# max78000_audio.net
KiCad netlist of a schematic drawn in EAGLE
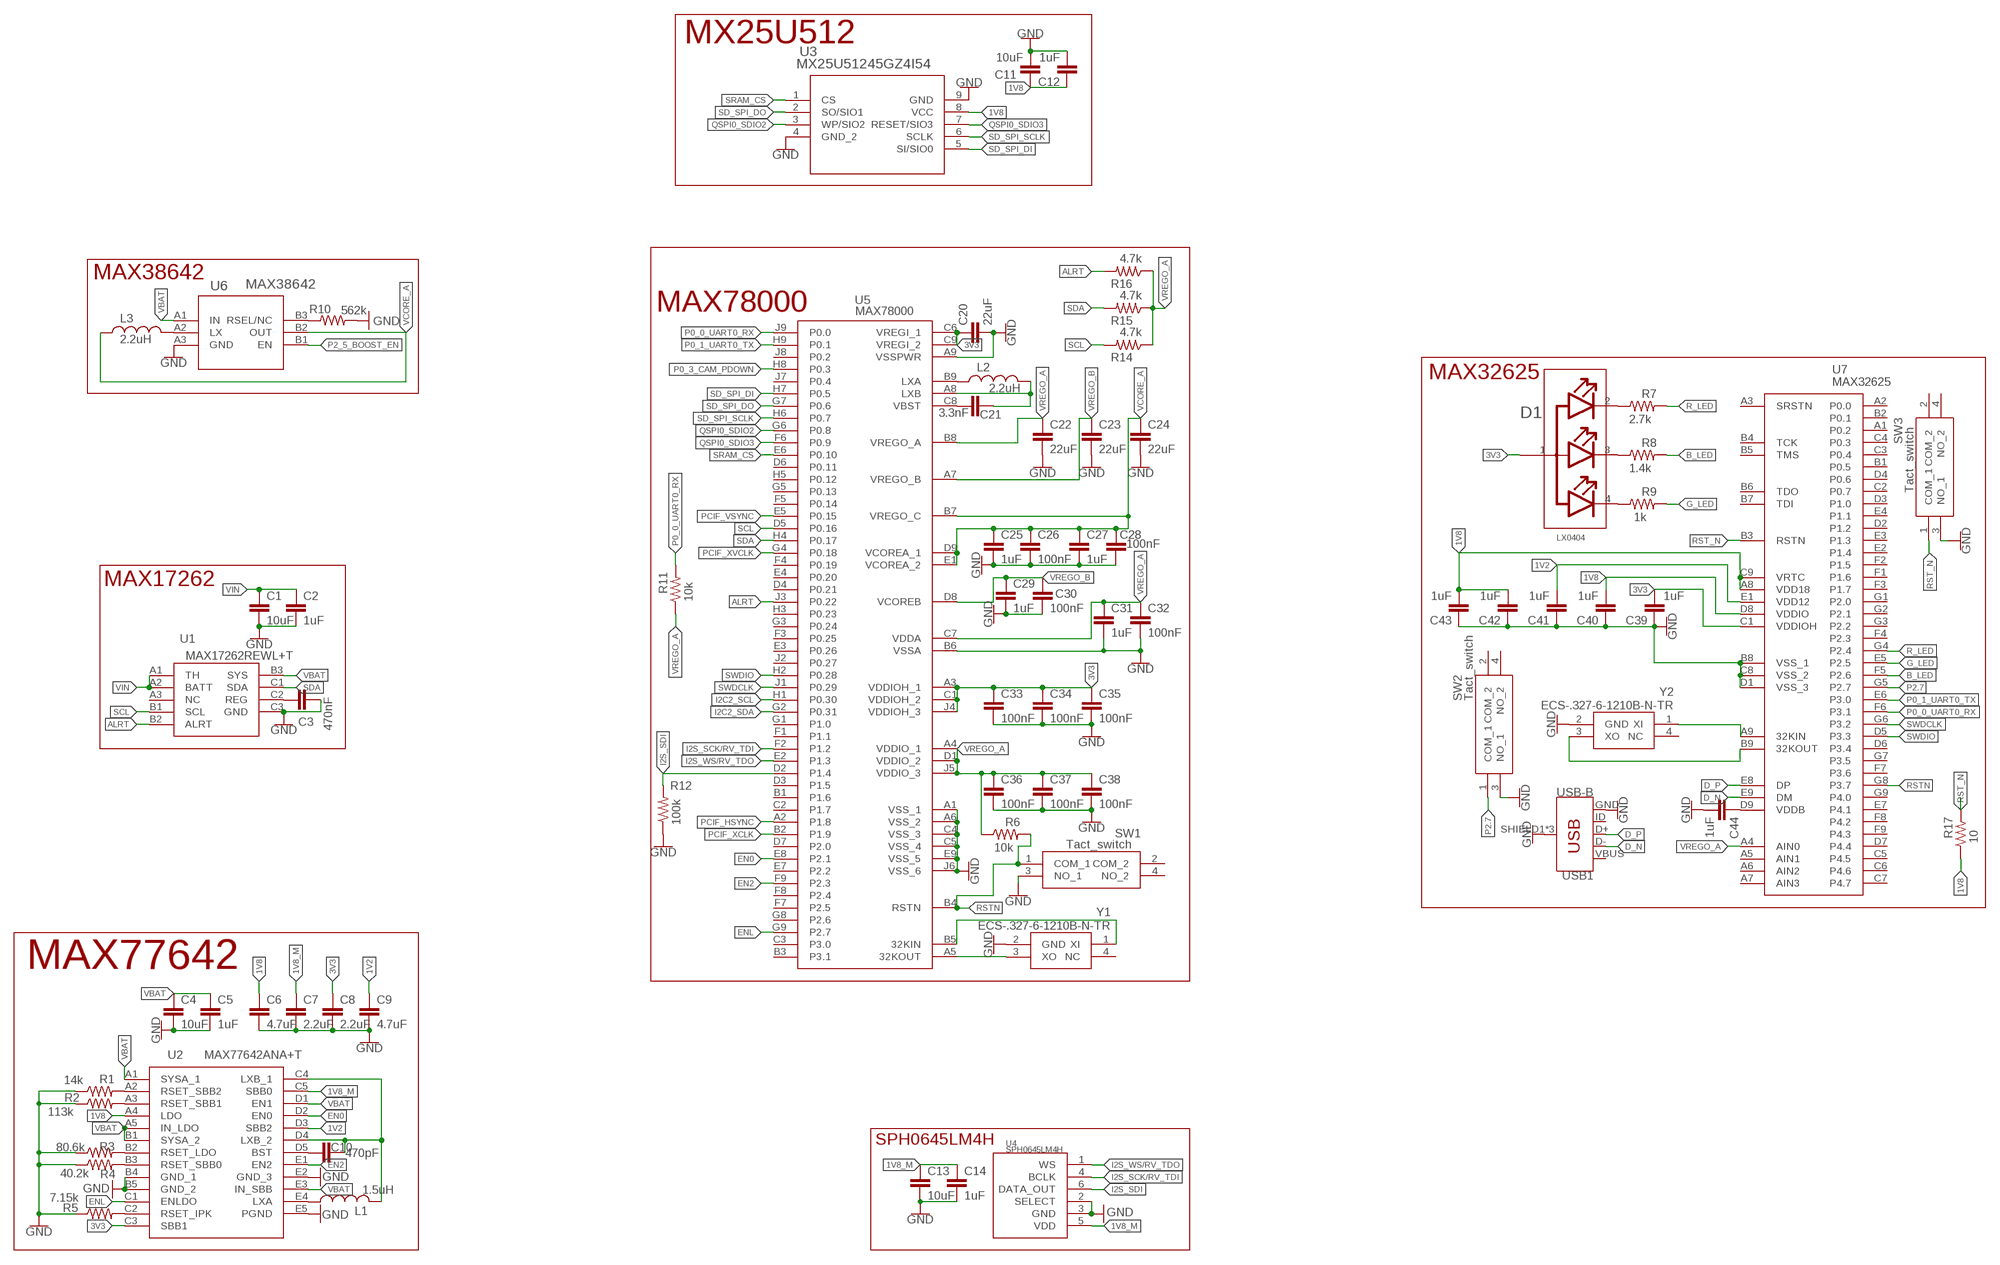
[diagram p0: schematic, sheet 1]

(export (version "E")
  (design (tool "Eeschema 10.0.6"))
  (components
    (comp (ref "C1")
      (value "10uF")
      (footprint "eagle-import:0402")
      (libsource (lib "eagle-import") (part "NPOL_SMD0402"))
    )
    (comp (ref "C2")
      (value "1uF")
      (footprint "eagle-import:0201")
      (libsource (lib "eagle-import") (part "NPOL_SMD0201"))
    )
    (comp (ref "C3")
      (value "470nF")
      (footprint "eagle-import:0201")
      (libsource (lib "eagle-import") (part "NPOL_SMD0201"))
    )
    (comp (ref "C4")
      (value "10uF")
      (footprint "eagle-import:0402")
      (libsource (lib "eagle-import") (part "NPOL_SMD0402"))
    )
    (comp (ref "C5")
      (value "1uF")
      (footprint "eagle-import:0201")
      (libsource (lib "eagle-import") (part "NPOL_SMD0201"))
    )
    (comp (ref "C6")
      (value "4.7uF")
      (footprint "eagle-import:0402")
      (libsource (lib "eagle-import") (part "NPOL_SMD0402"))
    )
    (comp (ref "C7")
      (value "2.2uF")
      (footprint "eagle-import:0402")
      (libsource (lib "eagle-import") (part "NPOL_SMD0402"))
    )
    (comp (ref "C8")
      (value "2.2uF")
      (footprint "eagle-import:0402")
      (libsource (lib "eagle-import") (part "NPOL_SMD0402"))
    )
    (comp (ref "C9")
      (value "4.7uF")
      (footprint "eagle-import:0402")
      (libsource (lib "eagle-import") (part "NPOL_SMD0402"))
    )
    (comp (ref "C10")
      (value "470pF")
      (footprint "eagle-import:0402")
      (libsource (lib "eagle-import") (part "NPOL_SMD0402"))
    )
    (comp (ref "C11")
      (value "10uF")
      (footprint "eagle-import:0201")
      (libsource (lib "eagle-import") (part "NPOL_SMD0201"))
    )
    (comp (ref "C12")
      (value "1uF")
      (footprint "eagle-import:0402")
      (libsource (lib "eagle-import") (part "NPOL_SMD0402"))
    )
    (comp (ref "C13")
      (value "10uF")
      (footprint "eagle-import:0402")
      (libsource (lib "eagle-import") (part "NPOL_SMD0402"))
    )
    (comp (ref "C14")
      (value "1uF")
      (footprint "eagle-import:0201")
      (libsource (lib "eagle-import") (part "NPOL_SMD0201"))
    )
    (comp (ref "C20")
      (value "22uF")
      (footprint "eagle-import:0603")
      (libsource (lib "eagle-import") (part "NPOL_SMD0603"))
    )
    (comp (ref "C21")
      (value "3.3nF")
      (footprint "eagle-import:0201")
      (libsource (lib "eagle-import") (part "NPOL_SMD0201"))
    )
    (comp (ref "C22")
      (value "22uF")
      (footprint "eagle-import:0603")
      (libsource (lib "eagle-import") (part "NPOL_SMD0603"))
    )
    (comp (ref "C23")
      (value "22uF")
      (footprint "eagle-import:0603")
      (libsource (lib "eagle-import") (part "NPOL_SMD0603"))
    )
    (comp (ref "C24")
      (value "22uF")
      (footprint "eagle-import:0603")
      (libsource (lib "eagle-import") (part "NPOL_SMD0603"))
    )
    (comp (ref "C25")
      (value "1uF")
      (footprint "eagle-import:0402")
      (libsource (lib "eagle-import") (part "NPOL_SMD0402"))
    )
    (comp (ref "C26")
      (value "100nF")
      (footprint "eagle-import:0201")
      (libsource (lib "eagle-import") (part "NPOL_SMD0201"))
    )
    (comp (ref "C27")
      (value "1uF")
      (footprint "eagle-import:0402")
      (libsource (lib "eagle-import") (part "NPOL_SMD0402"))
    )
    (comp (ref "C28")
      (value "100nF")
      (footprint "eagle-import:0201")
      (libsource (lib "eagle-import") (part "NPOL_SMD0201"))
    )
    (comp (ref "C29")
      (value "1uF")
      (footprint "eagle-import:0402")
      (libsource (lib "eagle-import") (part "NPOL_SMD0402"))
    )
    (comp (ref "C30")
      (value "100nF")
      (footprint "eagle-import:0201")
      (libsource (lib "eagle-import") (part "NPOL_SMD0201"))
    )
    (comp (ref "C31")
      (value "1uF")
      (footprint "eagle-import:0402")
      (libsource (lib "eagle-import") (part "NPOL_SMD0402"))
    )
    (comp (ref "C32")
      (value "100nF")
      (footprint "eagle-import:0201")
      (libsource (lib "eagle-import") (part "NPOL_SMD0201"))
    )
    (comp (ref "C33")
      (value "100nF")
      (footprint "eagle-import:0201")
      (libsource (lib "eagle-import") (part "NPOL_SMD0201"))
    )
    (comp (ref "C34")
      (value "100nF")
      (footprint "eagle-import:0201")
      (libsource (lib "eagle-import") (part "NPOL_SMD0201"))
    )
    (comp (ref "C35")
      (value "100nF")
      (footprint "eagle-import:0201")
      (libsource (lib "eagle-import") (part "NPOL_SMD0201"))
    )
    (comp (ref "C36")
      (value "100nF")
      (footprint "eagle-import:0201")
      (libsource (lib "eagle-import") (part "NPOL_SMD0201"))
    )
    (comp (ref "C37")
      (value "100nF")
      (footprint "eagle-import:0201")
      (libsource (lib "eagle-import") (part "NPOL_SMD0201"))
    )
    (comp (ref "C38")
      (value "100nF")
      (footprint "eagle-import:0201")
      (libsource (lib "eagle-import") (part "NPOL_SMD0201"))
    )
    (comp (ref "C39")
      (value "1uF")
      (footprint "eagle-import:0201")
      (libsource (lib "eagle-import") (part "NPOL_SMD0201"))
    )
    (comp (ref "C40")
      (value "1uF")
      (footprint "eagle-import:0201")
      (libsource (lib "eagle-import") (part "NPOL_SMD0201"))
    )
    (comp (ref "C41")
      (value "1uF")
      (footprint "eagle-import:0201")
      (libsource (lib "eagle-import") (part "NPOL_SMD0201"))
    )
    (comp (ref "C42")
      (value "1uF")
      (footprint "eagle-import:0201")
      (libsource (lib "eagle-import") (part "NPOL_SMD0201"))
    )
    (comp (ref "C43")
      (value "1uF")
      (footprint "eagle-import:0201")
      (libsource (lib "eagle-import") (part "NPOL_SMD0201"))
    )
    (comp (ref "C44")
      (value "1uF")
      (footprint "eagle-import:0201")
      (libsource (lib "eagle-import") (part "NPOL_SMD0201"))
    )
    (comp (ref "D1")
      (value "LX0404")
      (footprint "eagle-import:LUMEX_SML-LX0404SIUPGUSB_0")
      (fields
        (field (name "DIGIKEY_PART_NUMBER") "67-2125-1-ND")
        (field (name "MF") "Lumex")
        (field (name "MOUSER_PART_NUMBER") "696-LX0404SIUPGUSB")
      )
      (libsource (lib "eagle-import") (part "LUMEX_SML-LX0404SIUPGUSBLUMEX_SML-LX0404SIUPGUSB_0_0"))
    )
    (comp (ref "L1")
      (value "1.5uH")
      (footprint "eagle-import:0504")
      (libsource (lib "eagle-import") (part "SMD0504"))
    )
    (comp (ref "L2")
      (value "2.2uH")
      (footprint "eagle-import:0805")
      (libsource (lib "eagle-import") (part "SMD0805"))
    )
    (comp (ref "L3")
      (value "2.2uH")
      (footprint "eagle-import:0805")
      (libsource (lib "eagle-import") (part "SMD0805"))
    )
    (comp (ref "R1")
      (value "14k")
      (footprint "eagle-import:0201")
      (libsource (lib "eagle-import") (part "SMD0201"))
    )
    (comp (ref "R2")
      (value "113k")
      (footprint "eagle-import:0201")
      (libsource (lib "eagle-import") (part "SMD0201"))
    )
    (comp (ref "R3")
      (value "80.6k")
      (footprint "eagle-import:0201")
      (libsource (lib "eagle-import") (part "SMD0201"))
    )
    (comp (ref "R4")
      (value "40.2k")
      (footprint "eagle-import:0201")
      (libsource (lib "eagle-import") (part "SMD0201"))
    )
    (comp (ref "R5")
      (value "7.15k")
      (footprint "eagle-import:0201")
      (libsource (lib "eagle-import") (part "SMD0201"))
    )
    (comp (ref "R6")
      (value "10k")
      (footprint "eagle-import:0201")
      (libsource (lib "eagle-import") (part "SMD0201"))
    )
    (comp (ref "R7")
      (value "2.7k")
      (footprint "eagle-import:0201")
      (libsource (lib "eagle-import") (part "SMD0201"))
    )
    (comp (ref "R8")
      (value "1.4k")
      (footprint "eagle-import:0201")
      (libsource (lib "eagle-import") (part "SMD0201"))
    )
    (comp (ref "R9")
      (value "1k")
      (footprint "eagle-import:0201")
      (libsource (lib "eagle-import") (part "SMD0201"))
    )
    (comp (ref "R10")
      (value "562k")
      (footprint "eagle-import:0201")
      (libsource (lib "eagle-import") (part "SMD0201"))
    )
    (comp (ref "R11")
      (value "10k")
      (footprint "eagle-import:0201")
      (libsource (lib "eagle-import") (part "SMD0201"))
    )
    (comp (ref "R12")
      (value "100k")
      (footprint "eagle-import:0201")
      (libsource (lib "eagle-import") (part "SMD0201"))
    )
    (comp (ref "R14")
      (value "4.7k")
      (footprint "eagle-import:0201")
      (libsource (lib "eagle-import") (part "SMD0201"))
    )
    (comp (ref "R15")
      (value "4.7k")
      (footprint "eagle-import:0201")
      (libsource (lib "eagle-import") (part "SMD0201"))
    )
    (comp (ref "R16")
      (value "4.7k")
      (footprint "eagle-import:0201")
      (libsource (lib "eagle-import") (part "SMD0201"))
    )
    (comp (ref "R17")
      (value "10")
      (footprint "eagle-import:0201")
      (libsource (lib "eagle-import") (part "SMD0201"))
    )
    (comp (ref "SW1")
      (value "Tact_switch")
      (footprint "eagle-import:PTS815SJM250SMTRLFS")
      (libsource (lib "eagle-import") (part "PTS815_SJM_250_SMTR_LFS"))
    )
    (comp (ref "SW2")
      (value "Tact_switch")
      (footprint "eagle-import:PTS815SJM250SMTRLFS")
      (libsource (lib "eagle-import") (part "PTS815_SJM_250_SMTR_LFS"))
    )
    (comp (ref "SW3")
      (value "Tact_switch")
      (footprint "eagle-import:PTS815SJM250SMTRLFS")
      (libsource (lib "eagle-import") (part "PTS815_SJM_250_SMTR_LFS"))
    )
    (comp (ref "U1")
      (value "MAX17262REWL+T")
      (footprint "eagle-import:BGA9C40P3X3_147X145X69")
      (fields (field (name "MOUSER_PART_NUMBER") "700-MAX17262REWL+T"))
      (libsource (lib "eagle-import") (part "MAX17262REWL+T"))
    )
    (comp (ref "U2")
      (value "MAX77642ANA+T")
      (footprint "eagle-import:BGA25C40P5X5_206X206X50")
      (libsource (lib "eagle-import") (part "MAX77642ANA+T"))
    )
    (comp (ref "U3")
      (value "MX25U51245GZ4I54")
      (footprint "eagle-import:WSON8_8X6XOP8_MAC")
      (fields
        (field (name "MANUFACTURER_PART_NUMBER") "MX25U51245GZ4I00")
        (field (name "COPYRIGHT") "Copyright (C) 2018 Accelerated Designs. All rights reserved")
      )
      (libsource (lib "eagle-import") (part "MX25U51245GZ4I00"))
    )
    (comp (ref "U4")
      (value "SPH0645LM4H")
      (footprint "eagle-import:KNOWLES_SPH0645LM4H-B_0")
      (fields
        (field (name "DIGIKEY_PART_NUMBER") "423-1405-1-ND")
        (field (name "MF") "Knowles")
        (field (name "MOUSER_PART_NUMBER") "721-SPH0645LM4H-B")
      )
      (libsource (lib "eagle-import") (part "KNOWLES_SPH0645LM4H-BKNOWLES_SPH0645LM4H-B_0_0"))
    )
    (comp (ref "U5")
      (value "MAX78000")
      (footprint "eagle-import:BGA81C80P9X9_800X800X130")
      (fields
        (field (name "MANUFACTURER_PART_NUMBER") "MAX78000EXG+")
        (field (name "MOUSER_PART_NUMBER") "700-MAX78000EXG+")
      )
      (libsource (lib "eagle-import") (part "MAX78000EXG+"))
    )
    (comp (ref "U6")
      (value "MAX38642")
      (footprint "eagle-import:21-100128A_N60E1+2_MXM")
      (fields
        (field (name "MANUFACTURER_PART_NUMBER") "MAX38642AENT+")
        (field (name "COPYRIGHT") "Copyright (C) 2018 Accelerated Designs. All rights reserved")
      )
      (libsource (lib "eagle-import") (part "MAX38642AENT+"))
    )
    (comp (ref "U7")
      (value "MAX32625")
      (footprint "eagle-import:BGA63C40P9X7_387X307X69")
      (fields
        (field (name "MANUFACTURER_PART_NUMBER") "MAX32625IWY+T")
        (field (name "MOUSER_PART_NUMBER") "700-MAX32625IWY+T")
      )
      (libsource (lib "eagle-import") (part "MAX32625IWY+T"))
    )
    (comp (ref "USB1")
      (value "USB-B")
      (footprint "eagle-import:USB-B-MICRO-SMD")
      (libsource (lib "eagle-import") (part "USB_MICRO-B_FEMALE-SMT"))
    )
    (comp (ref "Y1")
      (value "ECS-.327-6-1210B-N-TR")
      (footprint "eagle-import:ECS32761210BNTR")
      (fields (field (name "MOUSER_PART_NUMBER") "520-ECS32761210BNTR"))
      (libsource (lib "eagle-import") (part "ECS-.327-6-1210B-N-TR"))
    )
    (comp (ref "Y2")
      (value "ECS-.327-6-1210B-N-TR")
      (footprint "eagle-import:ECS32761210BNTR")
      (fields (field (name "MOUSER_PART_NUMBER") "520-ECS32761210BNTR"))
      (libsource (lib "eagle-import") (part "ECS-.327-6-1210B-N-TR"))
    )
  )
  (nets
    (net (code "1") (name "/VBUS") (class "Default")
      (node (ref "USB1") (pin "VBUS") (pinfunction "VBUS_VBUS") (pintype "power_in"))
    )
    (net (code "2") (name "1V2") (class "Default")
      (node (ref "C41") (pin "2") (pinfunction "2_2") (pintype "passive"))
      (node (ref "C9") (pin "1") (pinfunction "1_1") (pintype "passive"))
      (node (ref "U2") (pin "D3") (pinfunction "SBB2_D3") (pintype "bidirectional"))
      (node (ref "U7") (pin "E1") (pinfunction "VDD12_E1") (pintype "bidirectional"))
    )
    (net (code "3") (name "1V8") (class "Default")
      (node (ref "C11") (pin "1") (pinfunction "1_1") (pintype "passive"))
      (node (ref "C12") (pin "1") (pinfunction "1_1") (pintype "passive"))
      (node (ref "C40") (pin "2") (pinfunction "2_2") (pintype "passive"))
      (node (ref "C42") (pin "2") (pinfunction "2_2") (pintype "passive"))
      (node (ref "C43") (pin "2") (pinfunction "2_2") (pintype "passive"))
      (node (ref "C6") (pin "1") (pinfunction "1_1") (pintype "passive"))
      (node (ref "R17") (pin "1") (pinfunction "1_1") (pintype "passive"))
      (node (ref "U2") (pin "A4") (pinfunction "LDO_A4") (pintype "bidirectional"))
      (node (ref "U3") (pin "8") (pinfunction "VCC_8") (pintype "power_in"))
      (node (ref "U7") (pin "A8") (pinfunction "VDD18_A8") (pintype "bidirectional"))
      (node (ref "U7") (pin "C9") (pinfunction "VRTC_C9") (pintype "bidirectional"))
      (node (ref "U7") (pin "D8") (pinfunction "VDDIO_D8") (pintype "bidirectional"))
    )
    (net (code "4") (name "1V8_M") (class "Default")
      (node (ref "C13") (pin "1") (pinfunction "1_1") (pintype "passive"))
      (node (ref "C14") (pin "1") (pinfunction "1_1") (pintype "passive"))
      (node (ref "C7") (pin "1") (pinfunction "1_1") (pintype "passive"))
      (node (ref "U2") (pin "C5") (pinfunction "SBB0_C5") (pintype "bidirectional"))
      (node (ref "U4") (pin "5") (pinfunction "VDD_5") (pintype "power_in"))
    )
    (net (code "5") (name "3V3") (class "Default")
      (node (ref "C20") (pin "1") (pinfunction "1_1") (pintype "passive"))
      (node (ref "C33") (pin "1") (pinfunction "1_1") (pintype "passive"))
      (node (ref "C34") (pin "1") (pinfunction "1_1") (pintype "passive"))
      (node (ref "C35") (pin "1") (pinfunction "1_1") (pintype "passive"))
      (node (ref "C39") (pin "2") (pinfunction "2_2") (pintype "passive"))
      (node (ref "C8") (pin "1") (pinfunction "1_1") (pintype "passive"))
      (node (ref "D1") (pin "1") (pinfunction "COMMON_ANODE_1") (pintype "passive"))
      (node (ref "U2") (pin "C3") (pinfunction "SBB1_C3") (pintype "bidirectional"))
      (node (ref "U5") (pin "A3") (pinfunction "VDDIOH_1_A3") (pintype "bidirectional"))
      (node (ref "U5") (pin "C1") (pinfunction "VDDIOH_2_C1") (pintype "bidirectional"))
      (node (ref "U5") (pin "C6") (pinfunction "VREGI_1_C6") (pintype "bidirectional"))
      (node (ref "U5") (pin "C9") (pinfunction "VREGI_2_C9") (pintype "bidirectional"))
      (node (ref "U5") (pin "J4") (pinfunction "VDDIOH_3_J4") (pintype "bidirectional"))
      (node (ref "U7") (pin "C1") (pinfunction "VDDIOH_C1") (pintype "bidirectional"))
    )
    (net (code "6") (name "ALRT") (class "Default")
      (node (ref "R16") (pin "2") (pinfunction "2_2") (pintype "passive"))
      (node (ref "U1") (pin "B2") (pinfunction "ALRT_B2") (pintype "bidirectional"))
      (node (ref "U5") (pin "J3") (pinfunction "P0.22_J3") (pintype "bidirectional"))
    )
    (net (code "7") (name "B_LED") (class "Default")
      (node (ref "R8") (pin "2") (pinfunction "2_2") (pintype "passive"))
      (node (ref "U7") (pin "F5") (pinfunction "P2.6_F5") (pintype "bidirectional"))
    )
    (net (code "8") (name "D_N") (class "Default")
      (node (ref "U7") (pin "E9") (pinfunction "DM_E9") (pintype "bidirectional"))
      (node (ref "USB1") (pin "D-") (pinfunction "D-_D-") (pintype "bidirectional"))
    )
    (net (code "9") (name "D_P") (class "Default")
      (node (ref "U7") (pin "E8") (pinfunction "DP_E8") (pintype "bidirectional"))
      (node (ref "USB1") (pin "D+") (pinfunction "D+_D+") (pintype "bidirectional"))
    )
    (net (code "10") (name "EN0") (class "Default")
      (node (ref "U2") (pin "D2") (pinfunction "EN0_D2") (pintype "bidirectional"))
      (node (ref "U5") (pin "E8") (pinfunction "P2.1_E8") (pintype "bidirectional"))
    )
    (net (code "11") (name "EN2") (class "Default")
      (node (ref "U2") (pin "E1") (pinfunction "EN2_E1") (pintype "bidirectional"))
      (node (ref "U5") (pin "F9") (pinfunction "P2.3_F9") (pintype "bidirectional"))
    )
    (net (code "12") (name "ENL") (class "Default")
      (node (ref "U2") (pin "C1") (pinfunction "ENLDO_C1") (pintype "bidirectional"))
      (node (ref "U5") (pin "G9") (pinfunction "P2.7_G9") (pintype "bidirectional"))
    )
    (net (code "13") (name "GND") (class "Default")
      (node (ref "C1") (pin "2") (pinfunction "2_2") (pintype "passive"))
      (node (ref "C11") (pin "2") (pinfunction "2_2") (pintype "passive"))
      (node (ref "C12") (pin "2") (pinfunction "2_2") (pintype "passive"))
      (node (ref "C13") (pin "2") (pinfunction "2_2") (pintype "passive"))
      (node (ref "C14") (pin "2") (pinfunction "2_2") (pintype "passive"))
      (node (ref "C2") (pin "2") (pinfunction "2_2") (pintype "passive"))
      (node (ref "C20") (pin "2") (pinfunction "2_2") (pintype "passive"))
      (node (ref "C22") (pin "2") (pinfunction "2_2") (pintype "passive"))
      (node (ref "C23") (pin "2") (pinfunction "2_2") (pintype "passive"))
      (node (ref "C24") (pin "2") (pinfunction "2_2") (pintype "passive"))
      (node (ref "C25") (pin "2") (pinfunction "2_2") (pintype "passive"))
      (node (ref "C26") (pin "2") (pinfunction "2_2") (pintype "passive"))
      (node (ref "C27") (pin "2") (pinfunction "2_2") (pintype "passive"))
      (node (ref "C28") (pin "2") (pinfunction "2_2") (pintype "passive"))
      (node (ref "C29") (pin "2") (pinfunction "2_2") (pintype "passive"))
      (node (ref "C3") (pin "2") (pinfunction "2_2") (pintype "passive"))
      (node (ref "C30") (pin "2") (pinfunction "2_2") (pintype "passive"))
      (node (ref "C31") (pin "2") (pinfunction "2_2") (pintype "passive"))
      (node (ref "C32") (pin "2") (pinfunction "2_2") (pintype "passive"))
      (node (ref "C33") (pin "2") (pinfunction "2_2") (pintype "passive"))
      (node (ref "C34") (pin "2") (pinfunction "2_2") (pintype "passive"))
      (node (ref "C35") (pin "2") (pinfunction "2_2") (pintype "passive"))
      (node (ref "C36") (pin "2") (pinfunction "2_2") (pintype "passive"))
      (node (ref "C37") (pin "2") (pinfunction "2_2") (pintype "passive"))
      (node (ref "C38") (pin "2") (pinfunction "2_2") (pintype "passive"))
      (node (ref "C39") (pin "1") (pinfunction "1_1") (pintype "passive"))
      (node (ref "C4") (pin "2") (pinfunction "2_2") (pintype "passive"))
      (node (ref "C40") (pin "1") (pinfunction "1_1") (pintype "passive"))
      (node (ref "C41") (pin "1") (pinfunction "1_1") (pintype "passive"))
      (node (ref "C42") (pin "1") (pinfunction "1_1") (pintype "passive"))
      (node (ref "C43") (pin "1") (pinfunction "1_1") (pintype "passive"))
      (node (ref "C44") (pin "2") (pinfunction "2_2") (pintype "passive"))
      (node (ref "C5") (pin "2") (pinfunction "2_2") (pintype "passive"))
      (node (ref "C6") (pin "2") (pinfunction "2_2") (pintype "passive"))
      (node (ref "C7") (pin "2") (pinfunction "2_2") (pintype "passive"))
      (node (ref "C8") (pin "2") (pinfunction "2_2") (pintype "passive"))
      (node (ref "C9") (pin "2") (pinfunction "2_2") (pintype "passive"))
      (node (ref "R1") (pin "1") (pinfunction "1_1") (pintype "passive"))
      (node (ref "R10") (pin "2") (pinfunction "2_2") (pintype "passive"))
      (node (ref "R12") (pin "1") (pinfunction "1_1") (pintype "passive"))
      (node (ref "R2") (pin "1") (pinfunction "1_1") (pintype "passive"))
      (node (ref "R3") (pin "1") (pinfunction "1_1") (pintype "passive"))
      (node (ref "R4") (pin "1") (pinfunction "1_1") (pintype "passive"))
      (node (ref "R5") (pin "1") (pinfunction "1_1") (pintype "passive"))
      (node (ref "SW1") (pin "3") (pinfunction "NO_1_3") (pintype "bidirectional"))
      (node (ref "SW2") (pin "3") (pinfunction "NO_1_3") (pintype "bidirectional"))
      (node (ref "SW3") (pin "3") (pinfunction "NO_1_3") (pintype "bidirectional"))
      (node (ref "U1") (pin "C3") (pinfunction "GND_C3") (pintype "bidirectional"))
      (node (ref "U2") (pin "B4") (pinfunction "GND_1_B4") (pintype "bidirectional"))
      (node (ref "U2") (pin "B5") (pinfunction "GND_2_B5") (pintype "bidirectional"))
      (node (ref "U2") (pin "E2") (pinfunction "GND_3_E2") (pintype "bidirectional"))
      (node (ref "U2") (pin "E5") (pinfunction "PGND_E5") (pintype "bidirectional"))
      (node (ref "U3") (pin "4") (pinfunction "GND_2_4") (pintype "passive"))
      (node (ref "U3") (pin "9") (pinfunction "GND_9") (pintype "passive"))
      (node (ref "U4") (pin "2") (pinfunction "SELECT_2") (pintype "input"))
      (node (ref "U4") (pin "3") (pinfunction "GND_3") (pintype "power_in"))
      (node (ref "U5") (pin "A1") (pinfunction "VSS_1_A1") (pintype "bidirectional"))
      (node (ref "U5") (pin "A6") (pinfunction "VSS_2_A6") (pintype "bidirectional"))
      (node (ref "U5") (pin "A9") (pinfunction "VSSPWR_A9") (pintype "bidirectional"))
      (node (ref "U5") (pin "B6") (pinfunction "VSSA_B6") (pintype "bidirectional"))
      (node (ref "U5") (pin "C4") (pinfunction "VSS_3_C4") (pintype "bidirectional"))
      (node (ref "U5") (pin "C5") (pinfunction "VSS_4_C5") (pintype "bidirectional"))
      (node (ref "U5") (pin "E9") (pinfunction "VSS_5_E9") (pintype "bidirectional"))
      (node (ref "U5") (pin "J6") (pinfunction "VSS_6_J6") (pintype "bidirectional"))
      (node (ref "U6") (pin "A3") (pinfunction "GND_A3") (pintype "passive"))
      (node (ref "U7") (pin "B8") (pinfunction "VSS_1_B8") (pintype "bidirectional"))
      (node (ref "U7") (pin "C8") (pinfunction "VSS_2_C8") (pintype "bidirectional"))
      (node (ref "U7") (pin "D1") (pinfunction "VSS_3_D1") (pintype "bidirectional"))
      (node (ref "USB1") (pin "GND") (pinfunction "GND_GND") (pintype "power_in"))
      (node (ref "USB1") (pin "SHIELD1") (pinfunction "SHIELD_SHIELD1") (pintype "bidirectional"))
      (node (ref "USB1") (pin "SHIELD2") (pinfunction "SHIELD_SHIELD2") (pintype "bidirectional"))
      (node (ref "USB1") (pin "SHIELD3") (pinfunction "SHIELD_SHIELD3") (pintype "bidirectional"))
      (node (ref "Y1") (pin "2") (pinfunction "GND_2") (pintype "bidirectional"))
      (node (ref "Y2") (pin "2") (pinfunction "GND_2") (pintype "bidirectional"))
    )
    (net (code "14") (name "G_LED") (class "Default")
      (node (ref "R9") (pin "2") (pinfunction "2_2") (pintype "passive"))
      (node (ref "U7") (pin "E5") (pinfunction "P2.5_E5") (pintype "bidirectional"))
    )
    (net (code "15") (name "I2C2_SCL") (class "Default")
      (node (ref "U5") (pin "H1") (pinfunction "P0.30_H1") (pintype "bidirectional"))
    )
    (net (code "16") (name "I2C2_SDA") (class "Default")
      (node (ref "U5") (pin "G2") (pinfunction "P0.31_G2") (pintype "bidirectional"))
    )
    (net (code "17") (name "I2S_SCK{slash}RV_TDI") (class "Default")
      (node (ref "U4") (pin "4") (pinfunction "BCLK_4") (pintype "input"))
      (node (ref "U5") (pin "F2") (pinfunction "P1.2_F2") (pintype "bidirectional"))
    )
    (net (code "18") (name "I2S_SDI") (class "Default")
      (node (ref "R12") (pin "2") (pinfunction "2_2") (pintype "passive"))
      (node (ref "U4") (pin "6") (pinfunction "DATA_OUT_6") (pintype "output"))
      (node (ref "U5") (pin "D2") (pinfunction "P1.4_D2") (pintype "bidirectional"))
    )
    (net (code "19") (name "I2S_WS{slash}RV_TDO") (class "Default")
      (node (ref "U4") (pin "1") (pinfunction "WS_1") (pintype "input"))
      (node (ref "U5") (pin "E2") (pinfunction "P1.3_E2") (pintype "bidirectional"))
    )
    (net (code "20") (name "Net-(D1-BLUE_CATHODE)") (class "Default")
      (node (ref "D1") (pin "3") (pinfunction "BLUE_CATHODE_3") (pintype "passive"))
      (node (ref "R8") (pin "1") (pinfunction "1_1") (pintype "passive"))
    )
    (net (code "21") (name "Net-(D1-GREEN_CATHODE)") (class "Default")
      (node (ref "D1") (pin "4") (pinfunction "GREEN_CATHODE_4") (pintype "passive"))
      (node (ref "R9") (pin "1") (pinfunction "1_1") (pintype "passive"))
    )
    (net (code "22") (name "Net-(D1-RED_CATHODE)") (class "Default")
      (node (ref "D1") (pin "2") (pinfunction "RED_CATHODE_2") (pintype "passive"))
      (node (ref "R7") (pin "1") (pinfunction "1_1") (pintype "passive"))
    )
    (net (code "23") (name "Net-(U1-REG)") (class "Default")
      (node (ref "C3") (pin "1") (pinfunction "1_1") (pintype "passive"))
      (node (ref "U1") (pin "C2") (pinfunction "REG_C2") (pintype "bidirectional"))
    )
    (net (code "24") (name "Net-(U2-BST)") (class "Default")
      (node (ref "C10") (pin "1") (pinfunction "1_1") (pintype "passive"))
      (node (ref "U2") (pin "D5") (pinfunction "BST_D5") (pintype "bidirectional"))
    )
    (net (code "25") (name "Net-(U2-LXA)") (class "Default")
      (node (ref "L1") (pin "1") (pinfunction "1_1") (pintype "passive"))
      (node (ref "U2") (pin "E4") (pinfunction "LXA_E4") (pintype "bidirectional"))
    )
    (net (code "26") (name "Net-(U2-LXB_1)") (class "Default")
      (node (ref "C10") (pin "2") (pinfunction "2_2") (pintype "passive"))
      (node (ref "L1") (pin "2") (pinfunction "2_2") (pintype "passive"))
      (node (ref "U2") (pin "C4") (pinfunction "LXB_1_C4") (pintype "bidirectional"))
      (node (ref "U2") (pin "D4") (pinfunction "LXB_2_D4") (pintype "bidirectional"))
    )
    (net (code "27") (name "Net-(U2-RSET_IPK)") (class "Default")
      (node (ref "R5") (pin "2") (pinfunction "2_2") (pintype "passive"))
      (node (ref "U2") (pin "C2") (pinfunction "RSET_IPK_C2") (pintype "bidirectional"))
    )
    (net (code "28") (name "Net-(U2-RSET_LDO)") (class "Default")
      (node (ref "R3") (pin "2") (pinfunction "2_2") (pintype "passive"))
      (node (ref "U2") (pin "B2") (pinfunction "RSET_LDO_B2") (pintype "bidirectional"))
    )
    (net (code "29") (name "Net-(U2-RSET_SBB0)") (class "Default")
      (node (ref "R4") (pin "2") (pinfunction "2_2") (pintype "passive"))
      (node (ref "U2") (pin "B3") (pinfunction "RSET_SBB0_B3") (pintype "bidirectional"))
    )
    (net (code "30") (name "Net-(U2-RSET_SBB1)") (class "Default")
      (node (ref "R2") (pin "2") (pinfunction "2_2") (pintype "passive"))
      (node (ref "U2") (pin "A3") (pinfunction "RSET_SBB1_A3") (pintype "bidirectional"))
    )
    (net (code "31") (name "Net-(U2-RSET_SBB2)") (class "Default")
      (node (ref "R1") (pin "2") (pinfunction "2_2") (pintype "passive"))
      (node (ref "U2") (pin "A2") (pinfunction "RSET_SBB2_A2") (pintype "bidirectional"))
    )
    (net (code "32") (name "Net-(U5-32KIN)") (class "Default")
      (node (ref "U5") (pin "B5") (pinfunction "32KIN_B5") (pintype "bidirectional"))
      (node (ref "Y1") (pin "1") (pinfunction "XI_1") (pintype "bidirectional"))
    )
    (net (code "33") (name "Net-(U5-32KOUT)") (class "Default")
      (node (ref "U5") (pin "A5") (pinfunction "32KOUT_A5") (pintype "bidirectional"))
      (node (ref "Y1") (pin "3") (pinfunction "XO_3") (pintype "bidirectional"))
    )
    (net (code "34") (name "Net-(U5-LXA)") (class "Default")
      (node (ref "L2") (pin "1") (pinfunction "1_1") (pintype "passive"))
      (node (ref "U5") (pin "B9") (pinfunction "LXA_B9") (pintype "bidirectional"))
    )
    (net (code "35") (name "Net-(U5-LXB)") (class "Default")
      (node (ref "C21") (pin "2") (pinfunction "2_2") (pintype "passive"))
      (node (ref "L2") (pin "2") (pinfunction "2_2") (pintype "passive"))
      (node (ref "U5") (pin "A8") (pinfunction "LXB_A8") (pintype "bidirectional"))
    )
    (net (code "36") (name "Net-(U5-VBST)") (class "Default")
      (node (ref "C21") (pin "1") (pinfunction "1_1") (pintype "passive"))
      (node (ref "U5") (pin "C8") (pinfunction "VBST_C8") (pintype "bidirectional"))
    )
    (net (code "37") (name "Net-(U6-LX)") (class "Default")
      (node (ref "L3") (pin "2") (pinfunction "2_2") (pintype "passive"))
      (node (ref "U6") (pin "A2") (pinfunction "LX_A2") (pintype "output"))
    )
    (net (code "38") (name "Net-(U6-RSEL{slash}NC)") (class "Default")
      (node (ref "R10") (pin "1") (pinfunction "1_1") (pintype "passive"))
      (node (ref "U6") (pin "B3") (pinfunction "RSEL/NC_B3") (pintype "bidirectional"))
    )
    (net (code "39") (name "Net-(U7-32KIN)") (class "Default")
      (node (ref "U7") (pin "A9") (pinfunction "32KIN_A9") (pintype "bidirectional"))
      (node (ref "Y2") (pin "1") (pinfunction "XI_1") (pintype "bidirectional"))
    )
    (net (code "40") (name "Net-(U7-32KOUT)") (class "Default")
      (node (ref "U7") (pin "B9") (pinfunction "32KOUT_B9") (pintype "bidirectional"))
      (node (ref "Y2") (pin "3") (pinfunction "XO_3") (pintype "bidirectional"))
    )
    (net (code "41") (name "Net-(U7-VDDB)") (class "Default")
      (node (ref "C44") (pin "1") (pinfunction "1_1") (pintype "passive"))
      (node (ref "U7") (pin "D9") (pinfunction "VDDB_D9") (pintype "bidirectional"))
    )
    (net (code "42") (name "P0_0_UART0_RX") (class "Default")
      (node (ref "R11") (pin "2") (pinfunction "2_2") (pintype "passive"))
      (node (ref "U5") (pin "J9") (pinfunction "P0.0_J9") (pintype "bidirectional"))
      (node (ref "U7") (pin "F6") (pinfunction "P3.1_F6") (pintype "bidirectional"))
    )
    (net (code "43") (name "P0_1_UART0_TX") (class "Default")
      (node (ref "U5") (pin "H9") (pinfunction "P0.1_H9") (pintype "bidirectional"))
      (node (ref "U7") (pin "E6") (pinfunction "P3.0_E6") (pintype "bidirectional"))
    )
    (net (code "44") (name "P0_3_CAM_PDOWN") (class "Default")
      (node (ref "U5") (pin "H8") (pinfunction "P0.3_H8") (pintype "bidirectional"))
    )
    (net (code "45") (name "P2.7") (class "Default")
      (node (ref "SW2") (pin "1") (pinfunction "COM_1_1") (pintype "bidirectional"))
      (node (ref "U7") (pin "G5") (pinfunction "P2.7_G5") (pintype "bidirectional"))
    )
    (net (code "46") (name "P2_5_BOOST_EN") (class "Default")
      (node (ref "U6") (pin "B1") (pinfunction "EN_B1") (pintype "input"))
    )
    (net (code "47") (name "PCIF_HSYNC") (class "Default")
      (node (ref "U5") (pin "A2") (pinfunction "P1.8_A2") (pintype "bidirectional"))
    )
    (net (code "48") (name "PCIF_VSYNC") (class "Default")
      (node (ref "U5") (pin "E5") (pinfunction "P0.15_E5") (pintype "bidirectional"))
    )
    (net (code "49") (name "PCIF_XCLK") (class "Default")
      (node (ref "U5") (pin "B2") (pinfunction "P1.9_B2") (pintype "bidirectional"))
    )
    (net (code "50") (name "PCIF_XVCLK") (class "Default")
      (node (ref "U5") (pin "G4") (pinfunction "P0.18_G4") (pintype "bidirectional"))
    )
    (net (code "51") (name "QSPI0_SDIO2") (class "Default")
      (node (ref "U3") (pin "3") (pinfunction "WP/SIO2_3") (pintype "bidirectional"))
      (node (ref "U5") (pin "G6") (pinfunction "P0.8_G6") (pintype "bidirectional"))
    )
    (net (code "52") (name "QSPI0_SDIO3") (class "Default")
      (node (ref "U3") (pin "7") (pinfunction "RESET/SIO3_7") (pintype "bidirectional"))
      (node (ref "U5") (pin "F6") (pinfunction "P0.9_F6") (pintype "bidirectional"))
    )
    (net (code "53") (name "RSTN") (class "Default")
      (node (ref "R6") (pin "2") (pinfunction "2_2") (pintype "passive"))
      (node (ref "SW1") (pin "1") (pinfunction "COM_1_1") (pintype "bidirectional"))
      (node (ref "U5") (pin "B4") (pinfunction "RSTN_B4") (pintype "bidirectional"))
      (node (ref "U7") (pin "G8") (pinfunction "P3.7_G8") (pintype "bidirectional"))
    )
    (net (code "54") (name "RST_N") (class "Default")
      (node (ref "R17") (pin "2") (pinfunction "2_2") (pintype "passive"))
      (node (ref "SW3") (pin "1") (pinfunction "COM_1_1") (pintype "bidirectional"))
      (node (ref "U7") (pin "B3") (pinfunction "RSTN_B3") (pintype "bidirectional"))
    )
    (net (code "55") (name "R_LED") (class "Default")
      (node (ref "R7") (pin "2") (pinfunction "2_2") (pintype "passive"))
      (node (ref "U7") (pin "G4") (pinfunction "P2.4_G4") (pintype "bidirectional"))
    )
    (net (code "56") (name "SCL") (class "Default")
      (node (ref "R14") (pin "2") (pinfunction "2_2") (pintype "passive"))
      (node (ref "U1") (pin "B1") (pinfunction "SCL_B1") (pintype "bidirectional"))
      (node (ref "U5") (pin "D5") (pinfunction "P0.16_D5") (pintype "bidirectional"))
    )
    (net (code "57") (name "SDA") (class "Default")
      (node (ref "R15") (pin "2") (pinfunction "2_2") (pintype "passive"))
      (node (ref "U1") (pin "C1") (pinfunction "SDA_C1") (pintype "bidirectional"))
      (node (ref "U5") (pin "H4") (pinfunction "P0.17_H4") (pintype "bidirectional"))
    )
    (net (code "58") (name "SD_SPI_DI") (class "Default")
      (node (ref "U3") (pin "5") (pinfunction "SI/SIO0_5") (pintype "bidirectional"))
      (node (ref "U5") (pin "H7") (pinfunction "P0.5_H7") (pintype "bidirectional"))
    )
    (net (code "59") (name "SD_SPI_DO") (class "Default")
      (node (ref "U3") (pin "2") (pinfunction "SO/SIO1_2") (pintype "bidirectional"))
      (node (ref "U5") (pin "G7") (pinfunction "P0.6_G7") (pintype "bidirectional"))
    )
    (net (code "60") (name "SD_SPI_SCLK") (class "Default")
      (node (ref "U3") (pin "6") (pinfunction "SCLK_6") (pintype "input"))
      (node (ref "U5") (pin "H6") (pinfunction "P0.7_H6") (pintype "bidirectional"))
    )
    (net (code "61") (name "SRAM_CS") (class "Default")
      (node (ref "U3") (pin "1") (pinfunction "CS_1") (pintype "input"))
      (node (ref "U5") (pin "E6") (pinfunction "P0.10_E6") (pintype "bidirectional"))
    )
    (net (code "62") (name "SWDCLK") (class "Default")
      (node (ref "U5") (pin "J1") (pinfunction "P0.29_J1") (pintype "bidirectional"))
      (node (ref "U7") (pin "G6") (pinfunction "P3.2_G6") (pintype "bidirectional"))
    )
    (net (code "63") (name "SWDIO") (class "Default")
      (node (ref "U5") (pin "H2") (pinfunction "P0.28_H2") (pintype "bidirectional"))
      (node (ref "U7") (pin "D5") (pinfunction "P3.3_D5") (pintype "bidirectional"))
    )
    (net (code "64") (name "VBAT") (class "Default")
      (node (ref "C4") (pin "1") (pinfunction "1_1") (pintype "passive"))
      (node (ref "C5") (pin "1") (pinfunction "1_1") (pintype "passive"))
      (node (ref "U1") (pin "B3") (pinfunction "SYS_B3") (pintype "bidirectional"))
      (node (ref "U2") (pin "A1") (pinfunction "SYSA_1_A1") (pintype "bidirectional"))
      (node (ref "U2") (pin "A5") (pinfunction "IN_LDO_A5") (pintype "bidirectional"))
      (node (ref "U2") (pin "B1") (pinfunction "SYSA_2_B1") (pintype "bidirectional"))
      (node (ref "U2") (pin "D1") (pinfunction "EN1_D1") (pintype "bidirectional"))
      (node (ref "U2") (pin "E3") (pinfunction "IN_SBB_E3") (pintype "bidirectional"))
      (node (ref "U6") (pin "A1") (pinfunction "IN_A1") (pintype "input"))
    )
    (net (code "65") (name "VCORE_A") (class "Default")
      (node (ref "C24") (pin "1") (pinfunction "1_1") (pintype "passive"))
      (node (ref "C25") (pin "1") (pinfunction "1_1") (pintype "passive"))
      (node (ref "C26") (pin "1") (pinfunction "1_1") (pintype "passive"))
      (node (ref "C27") (pin "1") (pinfunction "1_1") (pintype "passive"))
      (node (ref "C28") (pin "1") (pinfunction "1_1") (pintype "passive"))
      (node (ref "L3") (pin "1") (pinfunction "1_1") (pintype "passive"))
      (node (ref "U5") (pin "B7") (pinfunction "VREGO_C_B7") (pintype "bidirectional"))
      (node (ref "U5") (pin "D9") (pinfunction "VCOREA_1_D9") (pintype "bidirectional"))
      (node (ref "U5") (pin "E1") (pinfunction "VCOREA_2_E1") (pintype "bidirectional"))
      (node (ref "U6") (pin "B2") (pinfunction "OUT_B2") (pintype "output"))
    )
    (net (code "66") (name "VIN") (class "Default")
      (node (ref "C1") (pin "1") (pinfunction "1_1") (pintype "passive"))
      (node (ref "C2") (pin "1") (pinfunction "1_1") (pintype "passive"))
      (node (ref "U1") (pin "A1") (pinfunction "TH_A1") (pintype "bidirectional"))
      (node (ref "U1") (pin "A2") (pinfunction "BATT_A2") (pintype "bidirectional"))
    )
    (net (code "67") (name "VREGO_A") (class "Default")
      (node (ref "C22") (pin "1") (pinfunction "1_1") (pintype "passive"))
      (node (ref "C31") (pin "1") (pinfunction "1_1") (pintype "passive"))
      (node (ref "C32") (pin "1") (pinfunction "1_1") (pintype "passive"))
      (node (ref "C36") (pin "1") (pinfunction "1_1") (pintype "passive"))
      (node (ref "C37") (pin "1") (pinfunction "1_1") (pintype "passive"))
      (node (ref "C38") (pin "1") (pinfunction "1_1") (pintype "passive"))
      (node (ref "R11") (pin "1") (pinfunction "1_1") (pintype "passive"))
      (node (ref "R14") (pin "1") (pinfunction "1_1") (pintype "passive"))
      (node (ref "R15") (pin "1") (pinfunction "1_1") (pintype "passive"))
      (node (ref "R16") (pin "1") (pinfunction "1_1") (pintype "passive"))
      (node (ref "R6") (pin "1") (pinfunction "1_1") (pintype "passive"))
      (node (ref "U5") (pin "A4") (pinfunction "VDDIO_1_A4") (pintype "bidirectional"))
      (node (ref "U5") (pin "B8") (pinfunction "VREGO_A_B8") (pintype "bidirectional"))
      (node (ref "U5") (pin "C7") (pinfunction "VDDA_C7") (pintype "bidirectional"))
      (node (ref "U5") (pin "D1") (pinfunction "VDDIO_2_D1") (pintype "bidirectional"))
      (node (ref "U5") (pin "J5") (pinfunction "VDDIO_3_J5") (pintype "bidirectional"))
      (node (ref "U7") (pin "A4") (pinfunction "AIN0_A4") (pintype "bidirectional"))
    )
    (net (code "68") (name "VREGO_B") (class "Default")
      (node (ref "C23") (pin "1") (pinfunction "1_1") (pintype "passive"))
      (node (ref "C29") (pin "1") (pinfunction "1_1") (pintype "passive"))
      (node (ref "C30") (pin "1") (pinfunction "1_1") (pintype "passive"))
      (node (ref "U5") (pin "A7") (pinfunction "VREGO_B_A7") (pintype "bidirectional"))
      (node (ref "U5") (pin "D8") (pinfunction "VCOREB_D8") (pintype "bidirectional"))
    )
    (net (code "69") (name "unconnected-(SW1-COM_2-Pad2)") (class "Default")
      (node (ref "SW1") (pin "2") (pinfunction "COM_2_2") (pintype "bidirectional"))
    )
    (net (code "70") (name "unconnected-(SW1-NO_2-Pad4)") (class "Default")
      (node (ref "SW1") (pin "4") (pinfunction "NO_2_4") (pintype "bidirectional"))
    )
    (net (code "71") (name "unconnected-(SW2-COM_2-Pad2)") (class "Default")
      (node (ref "SW2") (pin "2") (pinfunction "COM_2_2") (pintype "bidirectional"))
    )
    (net (code "72") (name "unconnected-(SW2-NO_2-Pad4)") (class "Default")
      (node (ref "SW2") (pin "4") (pinfunction "NO_2_4") (pintype "bidirectional"))
    )
    (net (code "73") (name "unconnected-(SW3-COM_2-Pad2)") (class "Default")
      (node (ref "SW3") (pin "2") (pinfunction "COM_2_2") (pintype "bidirectional"))
    )
    (net (code "74") (name "unconnected-(SW3-NO_2-Pad4)") (class "Default")
      (node (ref "SW3") (pin "4") (pinfunction "NO_2_4") (pintype "bidirectional"))
    )
    (net (code "75") (name "unconnected-(U1-NC-PadA3)") (class "Default")
      (node (ref "U1") (pin "A3") (pinfunction "NC_A3") (pintype "no_connect"))
    )
    (net (code "76") (name "unconnected-(U5-P0.2-PadJ8)") (class "Default")
      (node (ref "U5") (pin "J8") (pinfunction "P0.2_J8") (pintype "bidirectional"))
    )
    (net (code "77") (name "unconnected-(U5-P0.4-PadJ7)") (class "Default")
      (node (ref "U5") (pin "J7") (pinfunction "P0.4_J7") (pintype "bidirectional"))
    )
    (net (code "78") (name "unconnected-(U5-P0.11-PadD6)") (class "Default")
      (node (ref "U5") (pin "D6") (pinfunction "P0.11_D6") (pintype "bidirectional"))
    )
    (net (code "79") (name "unconnected-(U5-P0.12-PadH5)") (class "Default")
      (node (ref "U5") (pin "H5") (pinfunction "P0.12_H5") (pintype "bidirectional"))
    )
    (net (code "80") (name "unconnected-(U5-P0.13-PadG5)") (class "Default")
      (node (ref "U5") (pin "G5") (pinfunction "P0.13_G5") (pintype "bidirectional"))
    )
    (net (code "81") (name "unconnected-(U5-P0.14-PadF5)") (class "Default")
      (node (ref "U5") (pin "F5") (pinfunction "P0.14_F5") (pintype "bidirectional"))
    )
    (net (code "82") (name "unconnected-(U5-P0.19-PadF4)") (class "Default")
      (node (ref "U5") (pin "F4") (pinfunction "P0.19_F4") (pintype "bidirectional"))
    )
    (net (code "83") (name "unconnected-(U5-P0.20-PadE4)") (class "Default")
      (node (ref "U5") (pin "E4") (pinfunction "P0.20_E4") (pintype "bidirectional"))
    )
    (net (code "84") (name "unconnected-(U5-P0.21-PadD4)") (class "Default")
      (node (ref "U5") (pin "D4") (pinfunction "P0.21_D4") (pintype "bidirectional"))
    )
    (net (code "85") (name "unconnected-(U5-P0.23-PadH3)") (class "Default")
      (node (ref "U5") (pin "H3") (pinfunction "P0.23_H3") (pintype "bidirectional"))
    )
    (net (code "86") (name "unconnected-(U5-P0.24-PadG3)") (class "Default")
      (node (ref "U5") (pin "G3") (pinfunction "P0.24_G3") (pintype "bidirectional"))
    )
    (net (code "87") (name "unconnected-(U5-P0.25-PadF3)") (class "Default")
      (node (ref "U5") (pin "F3") (pinfunction "P0.25_F3") (pintype "bidirectional"))
    )
    (net (code "88") (name "unconnected-(U5-P0.26-PadE3)") (class "Default")
      (node (ref "U5") (pin "E3") (pinfunction "P0.26_E3") (pintype "bidirectional"))
    )
    (net (code "89") (name "unconnected-(U5-P0.27-PadJ2)") (class "Default")
      (node (ref "U5") (pin "J2") (pinfunction "P0.27_J2") (pintype "bidirectional"))
    )
    (net (code "90") (name "unconnected-(U5-P1.0-PadG1)") (class "Default")
      (node (ref "U5") (pin "G1") (pinfunction "P1.0_G1") (pintype "bidirectional"))
    )
    (net (code "91") (name "unconnected-(U5-P1.1-PadF1)") (class "Default")
      (node (ref "U5") (pin "F1") (pinfunction "P1.1_F1") (pintype "bidirectional"))
    )
    (net (code "92") (name "unconnected-(U5-P1.5-PadD3)") (class "Default")
      (node (ref "U5") (pin "D3") (pinfunction "P1.5_D3") (pintype "bidirectional"))
    )
    (net (code "93") (name "unconnected-(U5-P1.6-PadB1)") (class "Default")
      (node (ref "U5") (pin "B1") (pinfunction "P1.6_B1") (pintype "bidirectional"))
    )
    (net (code "94") (name "unconnected-(U5-P1.7-PadC2)") (class "Default")
      (node (ref "U5") (pin "C2") (pinfunction "P1.7_C2") (pintype "bidirectional"))
    )
    (net (code "95") (name "unconnected-(U5-P2.0-PadD7)") (class "Default")
      (node (ref "U5") (pin "D7") (pinfunction "P2.0_D7") (pintype "bidirectional"))
    )
    (net (code "96") (name "unconnected-(U5-P2.2-PadE7)") (class "Default")
      (node (ref "U5") (pin "E7") (pinfunction "P2.2_E7") (pintype "bidirectional"))
    )
    (net (code "97") (name "unconnected-(U5-P2.4-PadF8)") (class "Default")
      (node (ref "U5") (pin "F8") (pinfunction "P2.4_F8") (pintype "bidirectional"))
    )
    (net (code "98") (name "unconnected-(U5-P2.5-PadF7)") (class "Default")
      (node (ref "U5") (pin "F7") (pinfunction "P2.5_F7") (pintype "bidirectional"))
    )
    (net (code "99") (name "unconnected-(U5-P2.6-PadG8)") (class "Default")
      (node (ref "U5") (pin "G8") (pinfunction "P2.6_G8") (pintype "bidirectional"))
    )
    (net (code "100") (name "unconnected-(U5-P3.0-PadC3)") (class "Default")
      (node (ref "U5") (pin "C3") (pinfunction "P3.0_C3") (pintype "bidirectional"))
    )
    (net (code "101") (name "unconnected-(U5-P3.1-PadB3)") (class "Default")
      (node (ref "U5") (pin "B3") (pinfunction "P3.1_B3") (pintype "bidirectional"))
    )
    (net (code "102") (name "unconnected-(U7-AIN1-PadA5)") (class "Default")
      (node (ref "U7") (pin "A5") (pinfunction "AIN1_A5") (pintype "bidirectional"))
    )
    (net (code "103") (name "unconnected-(U7-AIN2-PadA6)") (class "Default")
      (node (ref "U7") (pin "A6") (pinfunction "AIN2_A6") (pintype "bidirectional"))
    )
    (net (code "104") (name "unconnected-(U7-AIN3-PadA7)") (class "Default")
      (node (ref "U7") (pin "A7") (pinfunction "AIN3_A7") (pintype "bidirectional"))
    )
    (net (code "105") (name "unconnected-(U7-P0.0-PadA2)") (class "Default")
      (node (ref "U7") (pin "A2") (pinfunction "P0.0_A2") (pintype "bidirectional"))
    )
    (net (code "106") (name "unconnected-(U7-P0.1-PadB2)") (class "Default")
      (node (ref "U7") (pin "B2") (pinfunction "P0.1_B2") (pintype "bidirectional"))
    )
    (net (code "107") (name "unconnected-(U7-P0.2-PadA1)") (class "Default")
      (node (ref "U7") (pin "A1") (pinfunction "P0.2_A1") (pintype "bidirectional"))
    )
    (net (code "108") (name "unconnected-(U7-P0.3-PadC4)") (class "Default")
      (node (ref "U7") (pin "C4") (pinfunction "P0.3_C4") (pintype "bidirectional"))
    )
    (net (code "109") (name "unconnected-(U7-P0.4-PadC3)") (class "Default")
      (node (ref "U7") (pin "C3") (pinfunction "P0.4_C3") (pintype "bidirectional"))
    )
    (net (code "110") (name "unconnected-(U7-P0.5-PadB1)") (class "Default")
      (node (ref "U7") (pin "B1") (pinfunction "P0.5_B1") (pintype "bidirectional"))
    )
    (net (code "111") (name "unconnected-(U7-P0.6-PadD4)") (class "Default")
      (node (ref "U7") (pin "D4") (pinfunction "P0.6_D4") (pintype "bidirectional"))
    )
    (net (code "112") (name "unconnected-(U7-P0.7-PadC2)") (class "Default")
      (node (ref "U7") (pin "C2") (pinfunction "P0.7_C2") (pintype "bidirectional"))
    )
    (net (code "113") (name "unconnected-(U7-P1.0-PadD3)") (class "Default")
      (node (ref "U7") (pin "D3") (pinfunction "P1.0_D3") (pintype "bidirectional"))
    )
    (net (code "114") (name "unconnected-(U7-P1.1-PadE4)") (class "Default")
      (node (ref "U7") (pin "E4") (pinfunction "P1.1_E4") (pintype "bidirectional"))
    )
    (net (code "115") (name "unconnected-(U7-P1.2-PadD2)") (class "Default")
      (node (ref "U7") (pin "D2") (pinfunction "P1.2_D2") (pintype "bidirectional"))
    )
    (net (code "116") (name "unconnected-(U7-P1.3-PadE3)") (class "Default")
      (node (ref "U7") (pin "E3") (pinfunction "P1.3_E3") (pintype "bidirectional"))
    )
    (net (code "117") (name "unconnected-(U7-P1.4-PadE2)") (class "Default")
      (node (ref "U7") (pin "E2") (pinfunction "P1.4_E2") (pintype "bidirectional"))
    )
    (net (code "118") (name "unconnected-(U7-P1.5-PadF2)") (class "Default")
      (node (ref "U7") (pin "F2") (pinfunction "P1.5_F2") (pintype "bidirectional"))
    )
    (net (code "119") (name "unconnected-(U7-P1.6-PadF1)") (class "Default")
      (node (ref "U7") (pin "F1") (pinfunction "P1.6_F1") (pintype "bidirectional"))
    )
    (net (code "120") (name "unconnected-(U7-P1.7-PadF3)") (class "Default")
      (node (ref "U7") (pin "F3") (pinfunction "P1.7_F3") (pintype "bidirectional"))
    )
    (net (code "121") (name "unconnected-(U7-P2.0-PadG1)") (class "Default")
      (node (ref "U7") (pin "G1") (pinfunction "P2.0_G1") (pintype "bidirectional"))
    )
    (net (code "122") (name "unconnected-(U7-P2.1-PadG2)") (class "Default")
      (node (ref "U7") (pin "G2") (pinfunction "P2.1_G2") (pintype "bidirectional"))
    )
    (net (code "123") (name "unconnected-(U7-P2.2-PadG3)") (class "Default")
      (node (ref "U7") (pin "G3") (pinfunction "P2.2_G3") (pintype "bidirectional"))
    )
    (net (code "124") (name "unconnected-(U7-P2.3-PadF4)") (class "Default")
      (node (ref "U7") (pin "F4") (pinfunction "P2.3_F4") (pintype "bidirectional"))
    )
    (net (code "125") (name "unconnected-(U7-P3.4-PadD6)") (class "Default")
      (node (ref "U7") (pin "D6") (pinfunction "P3.4_D6") (pintype "bidirectional"))
    )
    (net (code "126") (name "unconnected-(U7-P3.5-PadG7)") (class "Default")
      (node (ref "U7") (pin "G7") (pinfunction "P3.5_G7") (pintype "bidirectional"))
    )
    (net (code "127") (name "unconnected-(U7-P3.6-PadF7)") (class "Default")
      (node (ref "U7") (pin "F7") (pinfunction "P3.6_F7") (pintype "bidirectional"))
    )
    (net (code "128") (name "unconnected-(U7-P4.0-PadG9)") (class "Default")
      (node (ref "U7") (pin "G9") (pinfunction "P4.0_G9") (pintype "bidirectional"))
    )
    (net (code "129") (name "unconnected-(U7-P4.1-PadE7)") (class "Default")
      (node (ref "U7") (pin "E7") (pinfunction "P4.1_E7") (pintype "bidirectional"))
    )
    (net (code "130") (name "unconnected-(U7-P4.2-PadF8)") (class "Default")
      (node (ref "U7") (pin "F8") (pinfunction "P4.2_F8") (pintype "bidirectional"))
    )
    (net (code "131") (name "unconnected-(U7-P4.3-PadF9)") (class "Default")
      (node (ref "U7") (pin "F9") (pinfunction "P4.3_F9") (pintype "bidirectional"))
    )
    (net (code "132") (name "unconnected-(U7-P4.4-PadD7)") (class "Default")
      (node (ref "U7") (pin "D7") (pinfunction "P4.4_D7") (pintype "bidirectional"))
    )
    (net (code "133") (name "unconnected-(U7-P4.5-PadC5)") (class "Default")
      (node (ref "U7") (pin "C5") (pinfunction "P4.5_C5") (pintype "bidirectional"))
    )
    (net (code "134") (name "unconnected-(U7-P4.6-PadC6)") (class "Default")
      (node (ref "U7") (pin "C6") (pinfunction "P4.6_C6") (pintype "bidirectional"))
    )
    (net (code "135") (name "unconnected-(U7-P4.7-PadC7)") (class "Default")
      (node (ref "U7") (pin "C7") (pinfunction "P4.7_C7") (pintype "bidirectional"))
    )
    (net (code "136") (name "unconnected-(U7-SRSTN-PadA3)") (class "Default")
      (node (ref "U7") (pin "A3") (pinfunction "SRSTN_A3") (pintype "bidirectional"))
    )
    (net (code "137") (name "unconnected-(U7-TCK-PadB4)") (class "Default")
      (node (ref "U7") (pin "B4") (pinfunction "TCK_B4") (pintype "bidirectional"))
    )
    (net (code "138") (name "unconnected-(U7-TDI-PadB7)") (class "Default")
      (node (ref "U7") (pin "B7") (pinfunction "TDI_B7") (pintype "bidirectional"))
    )
    (net (code "139") (name "unconnected-(U7-TDO-PadB6)") (class "Default")
      (node (ref "U7") (pin "B6") (pinfunction "TDO_B6") (pintype "bidirectional"))
    )
    (net (code "140") (name "unconnected-(U7-TMS-PadB5)") (class "Default")
      (node (ref "U7") (pin "B5") (pinfunction "TMS_B5") (pintype "bidirectional"))
    )
    (net (code "141") (name "unconnected-(USB1-PadID)") (class "Default")
      (node (ref "USB1") (pin "ID") (pinfunction "ID_ID") (pintype "bidirectional"))
    )
    (net (code "142") (name "unconnected-(Y1-NC-Pad4)") (class "Default")
      (node (ref "Y1") (pin "4") (pinfunction "NC_4") (pintype "bidirectional"))
    )
    (net (code "143") (name "unconnected-(Y2-NC-Pad4)") (class "Default")
      (node (ref "Y2") (pin "4") (pinfunction "NC_4") (pintype "bidirectional"))
    )
  )
)
